# SwitchBoard.net
KiCad netlist of a schematic drawn in EAGLE
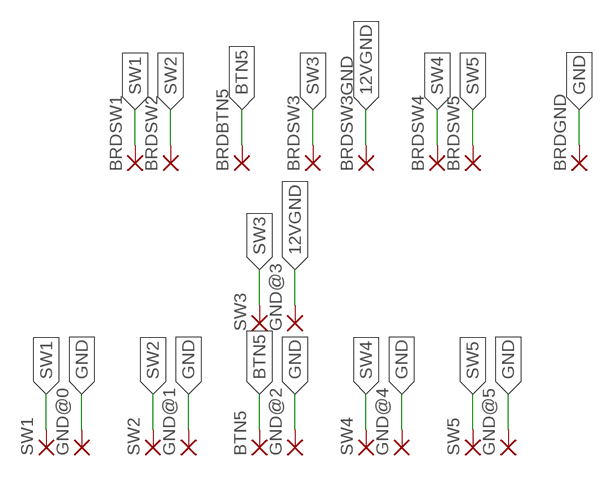
[diagram p0: schematic, sheet 1]

(export (version "E")
  (design (tool "Eeschema 10.0.6"))
  (components
    (comp (ref "BRDBTN5")
      (value "SMD5")
      (footprint "eagle-import:SMD2,54-5,08")
      (libsource (lib "eagle-import") (part "SMD5"))
    )
    (comp (ref "BRDGND")
      (value "SMD5")
      (footprint "eagle-import:SMD2,54-5,08")
      (libsource (lib "eagle-import") (part "SMD5"))
    )
    (comp (ref "BRDSW1")
      (value "SMD5")
      (footprint "eagle-import:SMD2,54-5,08")
      (libsource (lib "eagle-import") (part "SMD5"))
    )
    (comp (ref "BRDSW2")
      (value "SMD5")
      (footprint "eagle-import:SMD2,54-5,08")
      (libsource (lib "eagle-import") (part "SMD5"))
    )
    (comp (ref "BRDSW3")
      (value "SMD5")
      (footprint "eagle-import:SMD2,54-5,08")
      (libsource (lib "eagle-import") (part "SMD5"))
    )
    (comp (ref "BRDSW3GND")
      (value "SMD5")
      (footprint "eagle-import:SMD2,54-5,08")
      (libsource (lib "eagle-import") (part "SMD5"))
    )
    (comp (ref "BRDSW4")
      (value "SMD5")
      (footprint "eagle-import:SMD2,54-5,08")
      (libsource (lib "eagle-import") (part "SMD5"))
    )
    (comp (ref "BRDSW5")
      (value "SMD5")
      (footprint "eagle-import:SMD2,54-5,08")
      (libsource (lib "eagle-import") (part "SMD5"))
    )
    (comp (ref "BTN5")
      (value "SMD5")
      (footprint "eagle-import:SMD2,54-5,08")
      (libsource (lib "eagle-import") (part "SMD5"))
    )
    (comp (ref "GND@0")
      (value "SMD5")
      (footprint "eagle-import:SMD2,54-5,08")
      (libsource (lib "eagle-import") (part "SMD5"))
    )
    (comp (ref "GND@1")
      (value "SMD5")
      (footprint "eagle-import:SMD2,54-5,08")
      (libsource (lib "eagle-import") (part "SMD5"))
    )
    (comp (ref "GND@2")
      (value "SMD5")
      (footprint "eagle-import:SMD2,54-5,08")
      (libsource (lib "eagle-import") (part "SMD5"))
    )
    (comp (ref "GND@3")
      (value "SMD5")
      (footprint "eagle-import:SMD2,54-5,08")
      (libsource (lib "eagle-import") (part "SMD5"))
    )
    (comp (ref "GND@4")
      (value "SMD5")
      (footprint "eagle-import:SMD2,54-5,08")
      (libsource (lib "eagle-import") (part "SMD5"))
    )
    (comp (ref "GND@5")
      (value "SMD5")
      (footprint "eagle-import:SMD2,54-5,08")
      (libsource (lib "eagle-import") (part "SMD5"))
    )
    (comp (ref "SW1")
      (value "SMD5")
      (footprint "eagle-import:SMD2,54-5,08")
      (libsource (lib "eagle-import") (part "SMD5"))
    )
    (comp (ref "SW2")
      (value "SMD5")
      (footprint "eagle-import:SMD2,54-5,08")
      (libsource (lib "eagle-import") (part "SMD5"))
    )
    (comp (ref "SW3")
      (value "SMD5")
      (footprint "eagle-import:SMD2,54-5,08")
      (libsource (lib "eagle-import") (part "SMD5"))
    )
    (comp (ref "SW4")
      (value "SMD5")
      (footprint "eagle-import:SMD2,54-5,08")
      (libsource (lib "eagle-import") (part "SMD5"))
    )
    (comp (ref "SW5")
      (value "SMD5")
      (footprint "eagle-import:SMD2,54-5,08")
      (libsource (lib "eagle-import") (part "SMD5"))
    )
  )
  (nets
    (net (code "1") (name "12VGND") (class "Default")
      (node (ref "BRDSW3GND") (pin "1") (pinfunction "P_1") (pintype "passive"))
      (node (ref "GND@3") (pin "1") (pinfunction "P_1") (pintype "passive"))
    )
    (net (code "2") (name "BTN5") (class "Default")
      (node (ref "BRDBTN5") (pin "1") (pinfunction "P_1") (pintype "passive"))
      (node (ref "BTN5") (pin "1") (pinfunction "P_1") (pintype "passive"))
    )
    (net (code "3") (name "GND") (class "Default")
      (node (ref "BRDGND") (pin "1") (pinfunction "P_1") (pintype "passive"))
      (node (ref "GND@0") (pin "1") (pinfunction "P_1") (pintype "passive"))
      (node (ref "GND@1") (pin "1") (pinfunction "P_1") (pintype "passive"))
      (node (ref "GND@2") (pin "1") (pinfunction "P_1") (pintype "passive"))
      (node (ref "GND@4") (pin "1") (pinfunction "P_1") (pintype "passive"))
      (node (ref "GND@5") (pin "1") (pinfunction "P_1") (pintype "passive"))
    )
    (net (code "4") (name "SW1") (class "Default")
      (node (ref "BRDSW1") (pin "1") (pinfunction "P_1") (pintype "passive"))
      (node (ref "SW1") (pin "1") (pinfunction "P_1") (pintype "passive"))
    )
    (net (code "5") (name "SW2") (class "Default")
      (node (ref "BRDSW2") (pin "1") (pinfunction "P_1") (pintype "passive"))
      (node (ref "SW2") (pin "1") (pinfunction "P_1") (pintype "passive"))
    )
    (net (code "6") (name "SW3") (class "Default")
      (node (ref "BRDSW3") (pin "1") (pinfunction "P_1") (pintype "passive"))
      (node (ref "SW3") (pin "1") (pinfunction "P_1") (pintype "passive"))
    )
    (net (code "7") (name "SW4") (class "Default")
      (node (ref "BRDSW4") (pin "1") (pinfunction "P_1") (pintype "passive"))
      (node (ref "SW4") (pin "1") (pinfunction "P_1") (pintype "passive"))
    )
    (net (code "8") (name "SW5") (class "Default")
      (node (ref "BRDSW5") (pin "1") (pinfunction "P_1") (pintype "passive"))
      (node (ref "SW5") (pin "1") (pinfunction "P_1") (pintype "passive"))
    )
  )
)
